# LoRa.net
KiCad netlist of a schematic drawn in Altium Designer
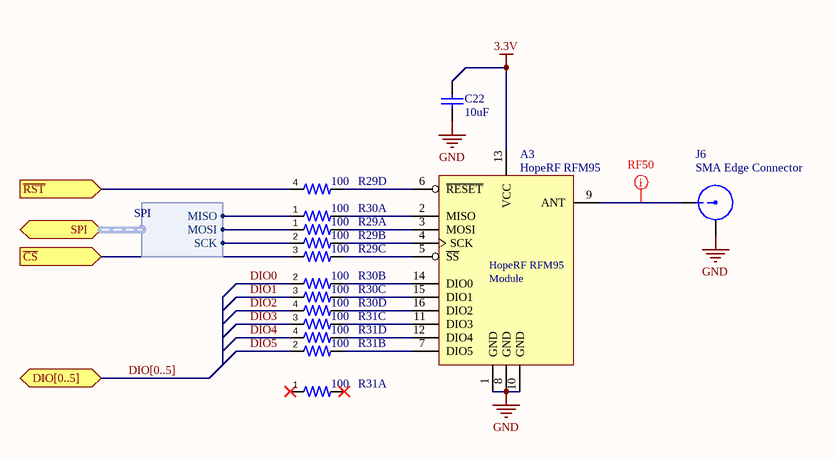
[diagram p0: LoRa.SchDoc]

(export (version "E")
  (design (tool "Eeschema 10.0.6"))
  (components
    (comp (ref "A3")
      (value "HopeRF RFM95")
      (footprint "RFM95/9697/98W")
      (description "HopeRF RFM95 915MHz LoRa Radio")
      (libsource (lib "Modules") (part "RFM95"))
    )
    (comp (ref "C22")
      (value "10uF")
      (footprint "CAPC2013X14L - CAP0805 1.45mm Tall")
      (description "SMT 0805 Ceramic Capacitor")
      (fields (field (name "TOLERANCE") "10%") (field (name "VOLTAGE") "6.3V"))
      (libsource (lib "Passives") (part "CAP0805 10uF 10% 6.3V X5R"))
    )
    (comp (ref "J6")
      (value "SMA Edge Connector")
      (footprint "SMA Connector - Edge Mount")
      (libsource (lib "Connectors") (part "SMA Edge Connector"))
    )
    (comp (ref "R29")
      (value "100")
      (footprint "CAC-80P319X159-8L")
      (fields (field (name "TOLERANCE") "5%") (field (name "POWER") "1/16W"))
      (libsource (lib "Passives") (part "RESARR1206 100 5% 1/16W"))
    )
    (comp (ref "R30")
      (value "100")
      (footprint "CAC-80P319X159-8L")
      (fields (field (name "TOLERANCE") "5%") (field (name "POWER") "1/16W"))
      (libsource (lib "Passives") (part "RESARR1206 100 5% 1/16W"))
    )
    (comp (ref "R31")
      (value "100")
      (footprint "CAC-80P319X159-8L")
      (fields (field (name "TOLERANCE") "5%") (field (name "POWER") "1/16W"))
      (libsource (lib "Passives") (part "RESARR1206 100 5% 1/16W"))
    )
  )
  (nets
    (net (code "2") (name "/DIO0") (class "Default")
      (node (ref "R30") (pin "2") (pinfunction "2_2") (pintype "passive"))
    )
    (net (code "3") (name "/DIO1") (class "Default")
      (node (ref "R30") (pin "3") (pinfunction "3_3") (pintype "passive"))
    )
    (net (code "4") (name "/DIO2") (class "Default")
      (node (ref "R30") (pin "4") (pinfunction "4_4") (pintype "passive"))
    )
    (net (code "5") (name "/DIO3") (class "Default")
      (node (ref "R31") (pin "3") (pinfunction "3_3") (pintype "passive"))
    )
    (net (code "6") (name "/DIO4") (class "Default")
      (node (ref "R31") (pin "4") (pinfunction "4_4") (pintype "passive"))
    )
    (net (code "7") (name "/DIO5") (class "Default")
      (node (ref "R31") (pin "2") (pinfunction "2_2") (pintype "passive"))
    )
    (net (code "9") (name "/MISO") (class "Default")
      (node (ref "R30") (pin "1") (pinfunction "1_1") (pintype "passive"))
    )
    (net (code "10") (name "/MOSI") (class "Default")
      (node (ref "R29") (pin "1") (pinfunction "1_1") (pintype "passive"))
    )
    (net (code "11") (name "/SCK") (class "Default")
      (node (ref "R29") (pin "2") (pinfunction "2_2") (pintype "passive"))
    )
    (net (code "13") (name "/~{CS}") (class "Default")
      (node (ref "R29") (pin "3") (pinfunction "3_3") (pintype "passive"))
    )
    (net (code "14") (name "/~{RST}") (class "Default")
      (node (ref "R29") (pin "4") (pinfunction "4_4") (pintype "passive"))
    )
    (net (code "15") (name "3.3V") (class "Default")
      (node (ref "A3") (pin "13") (pinfunction "VCC_13") (pintype "passive"))
      (node (ref "C22") (pin "2") (pinfunction "2_2") (pintype "passive"))
    )
    (net (code "16") (name "GND") (class "Default")
      (node (ref "A3") (pin "1") (pinfunction "GND_1") (pintype "passive"))
      (node (ref "A3") (pin "10") (pinfunction "GND_10") (pintype "passive"))
      (node (ref "A3") (pin "8") (pinfunction "GND_8") (pintype "passive"))
      (node (ref "C22") (pin "1") (pinfunction "1_1") (pintype "passive"))
      (node (ref "J6") (pin "2") (pinfunction "GND_2") (pintype "passive"))
    )
    (net (code "17") (name "Net-(A3-ANT)") (class "Default")
      (node (ref "A3") (pin "9") (pinfunction "ANT_9") (pintype "passive"))
      (node (ref "J6") (pin "1") (pinfunction "Signal_1") (pintype "passive"))
    )
    (net (code "18") (name "Net-(A3-DIO0)") (class "Default")
      (node (ref "A3") (pin "14") (pinfunction "DIO0_14") (pintype "passive"))
      (node (ref "R30") (pin "7") (pinfunction "7_7") (pintype "passive"))
    )
    (net (code "19") (name "Net-(A3-DIO1)") (class "Default")
      (node (ref "A3") (pin "15") (pinfunction "DIO1_15") (pintype "passive"))
      (node (ref "R30") (pin "6") (pinfunction "6_6") (pintype "passive"))
    )
    (net (code "20") (name "Net-(A3-DIO2)") (class "Default")
      (node (ref "A3") (pin "16") (pinfunction "DIO2_16") (pintype "passive"))
      (node (ref "R30") (pin "5") (pinfunction "5_5") (pintype "passive"))
    )
    (net (code "21") (name "Net-(A3-DIO3)") (class "Default")
      (node (ref "A3") (pin "11") (pinfunction "DIO3_11") (pintype "passive"))
      (node (ref "R31") (pin "6") (pinfunction "6_6") (pintype "passive"))
    )
    (net (code "22") (name "Net-(A3-DIO4)") (class "Default")
      (node (ref "A3") (pin "12") (pinfunction "DIO4_12") (pintype "passive"))
      (node (ref "R31") (pin "5") (pinfunction "5_5") (pintype "passive"))
    )
    (net (code "23") (name "Net-(A3-DIO5)") (class "Default")
      (node (ref "A3") (pin "7") (pinfunction "DIO5_7") (pintype "passive"))
      (node (ref "R31") (pin "7") (pinfunction "7_7") (pintype "passive"))
    )
    (net (code "24") (name "Net-(A3-MISO)") (class "Default")
      (node (ref "A3") (pin "2") (pinfunction "MISO_2") (pintype "passive"))
      (node (ref "R30") (pin "8") (pinfunction "8_8") (pintype "passive"))
    )
    (net (code "25") (name "Net-(A3-MOSI)") (class "Default")
      (node (ref "A3") (pin "3") (pinfunction "MOSI_3") (pintype "passive"))
      (node (ref "R29") (pin "8") (pinfunction "8_8") (pintype "passive"))
    )
    (net (code "26") (name "Net-(A3-SCK)") (class "Default")
      (node (ref "A3") (pin "4") (pinfunction "SCK_4") (pintype "passive"))
      (node (ref "R29") (pin "7") (pinfunction "7_7") (pintype "passive"))
    )
    (net (code "27") (name "Net-(A3-~{RESET})") (class "Default")
      (node (ref "A3") (pin "6") (pinfunction "~{RESET}_6") (pintype "passive"))
      (node (ref "R29") (pin "5") (pinfunction "5_5") (pintype "passive"))
    )
    (net (code "28") (name "Net-(A3-~{SS})") (class "Default")
      (node (ref "A3") (pin "5") (pinfunction "~{SS}_5") (pintype "passive"))
      (node (ref "R29") (pin "6") (pinfunction "6_6") (pintype "passive"))
    )
    (net (code "29") (name "unconnected-(R31-Pad1)") (class "Default")
      (node (ref "R31") (pin "1") (pinfunction "1_1") (pintype "passive+no_connect"))
    )
    (net (code "30") (name "unconnected-(R31-Pad8)") (class "Default")
      (node (ref "R31") (pin "8") (pinfunction "8_8") (pintype "passive+no_connect"))
    )
  )
)
